# microphone.net
KiCad netlist of a schematic drawn in Altium Designer
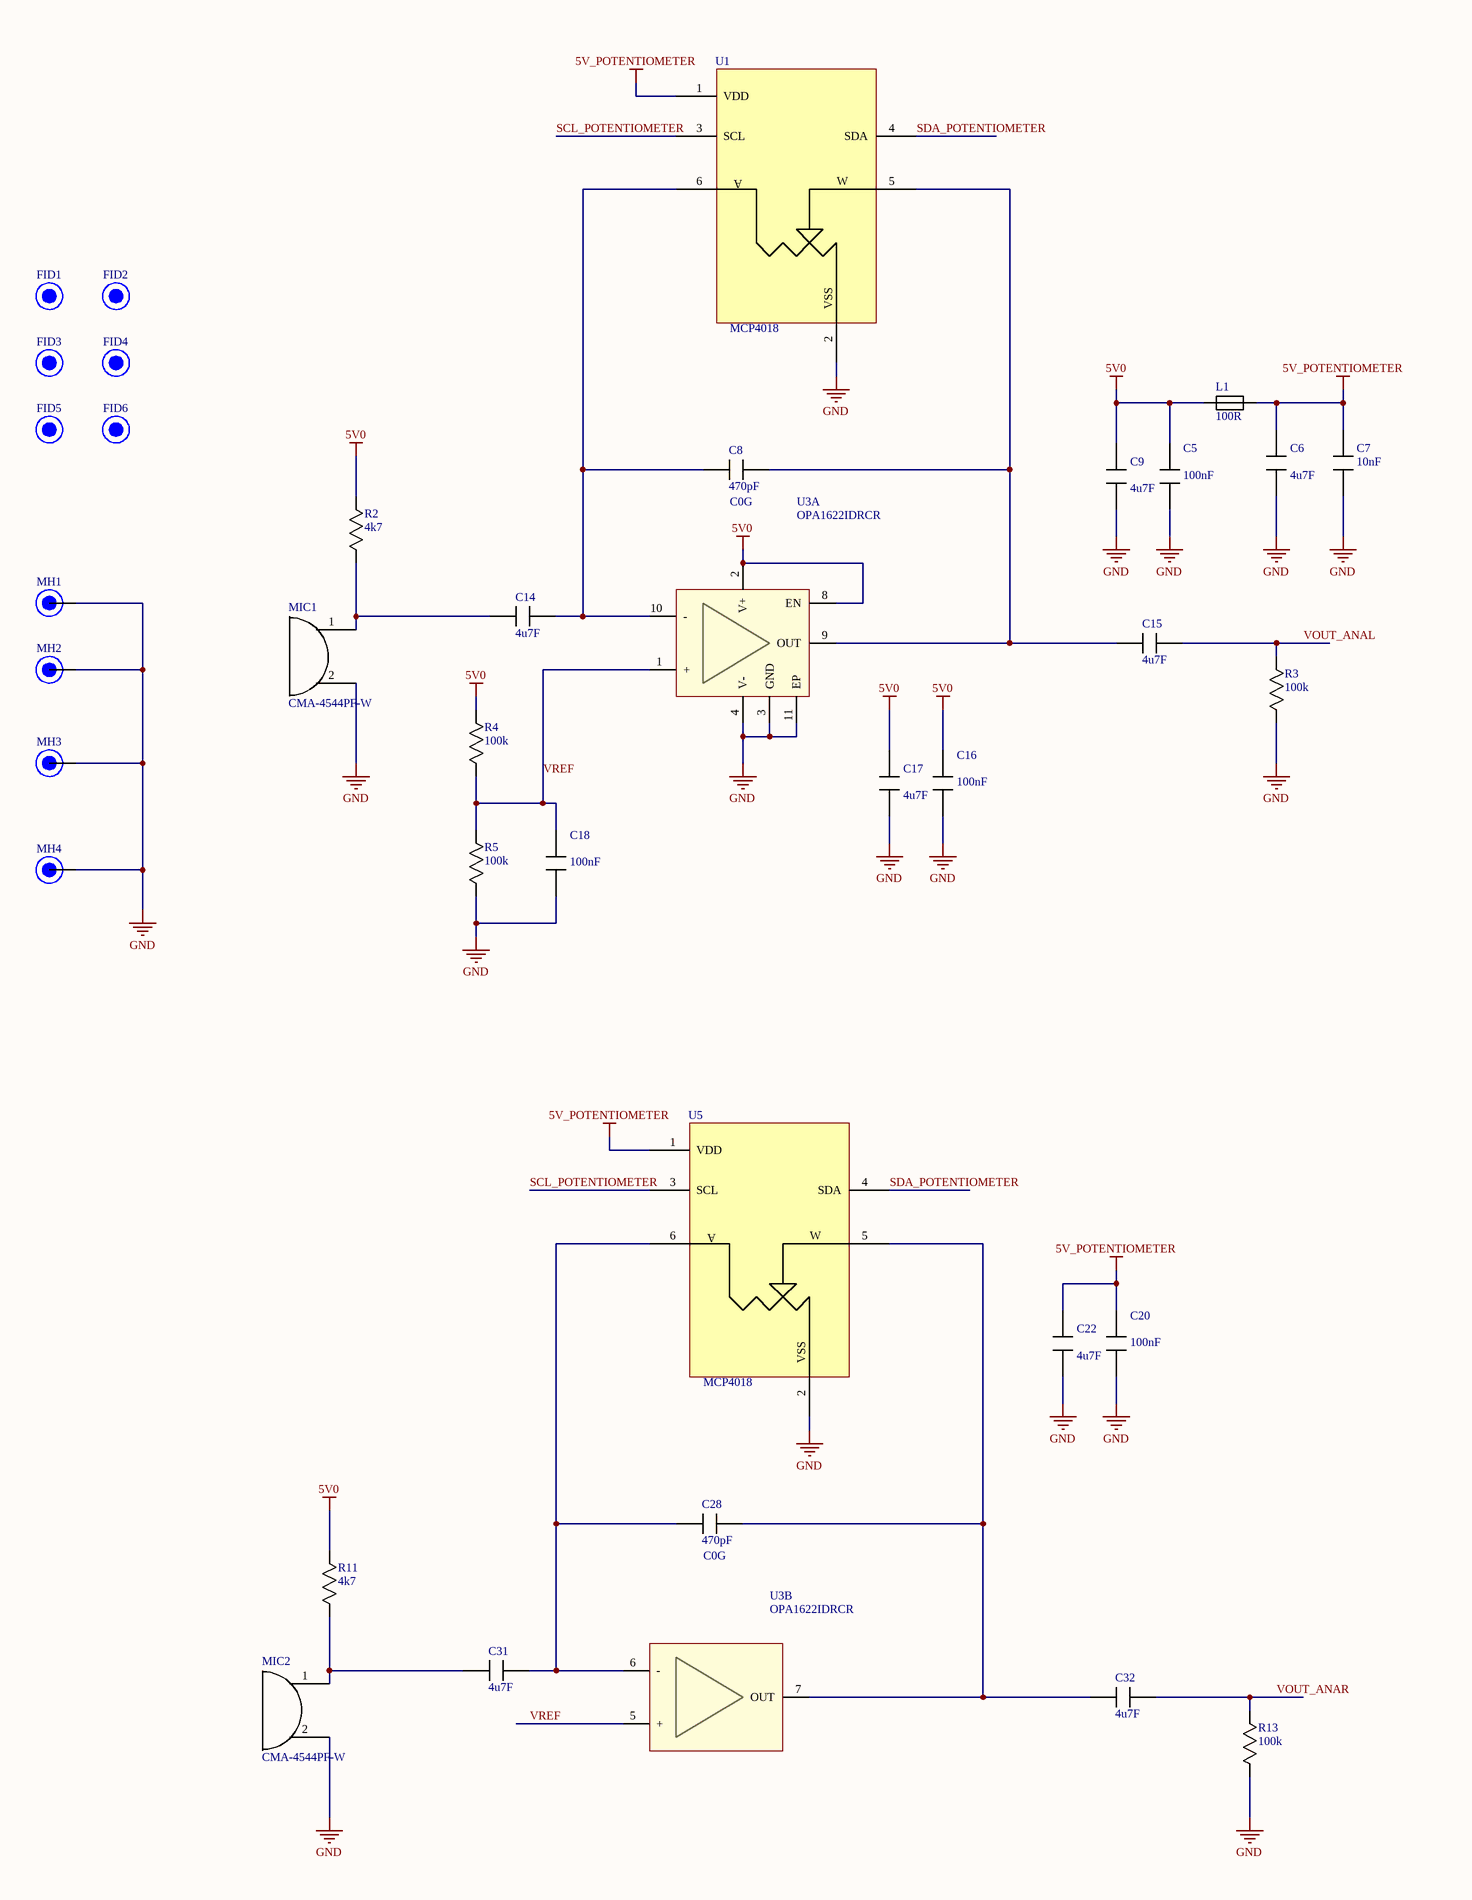
[diagram p0: microphone.SchDoc, left]
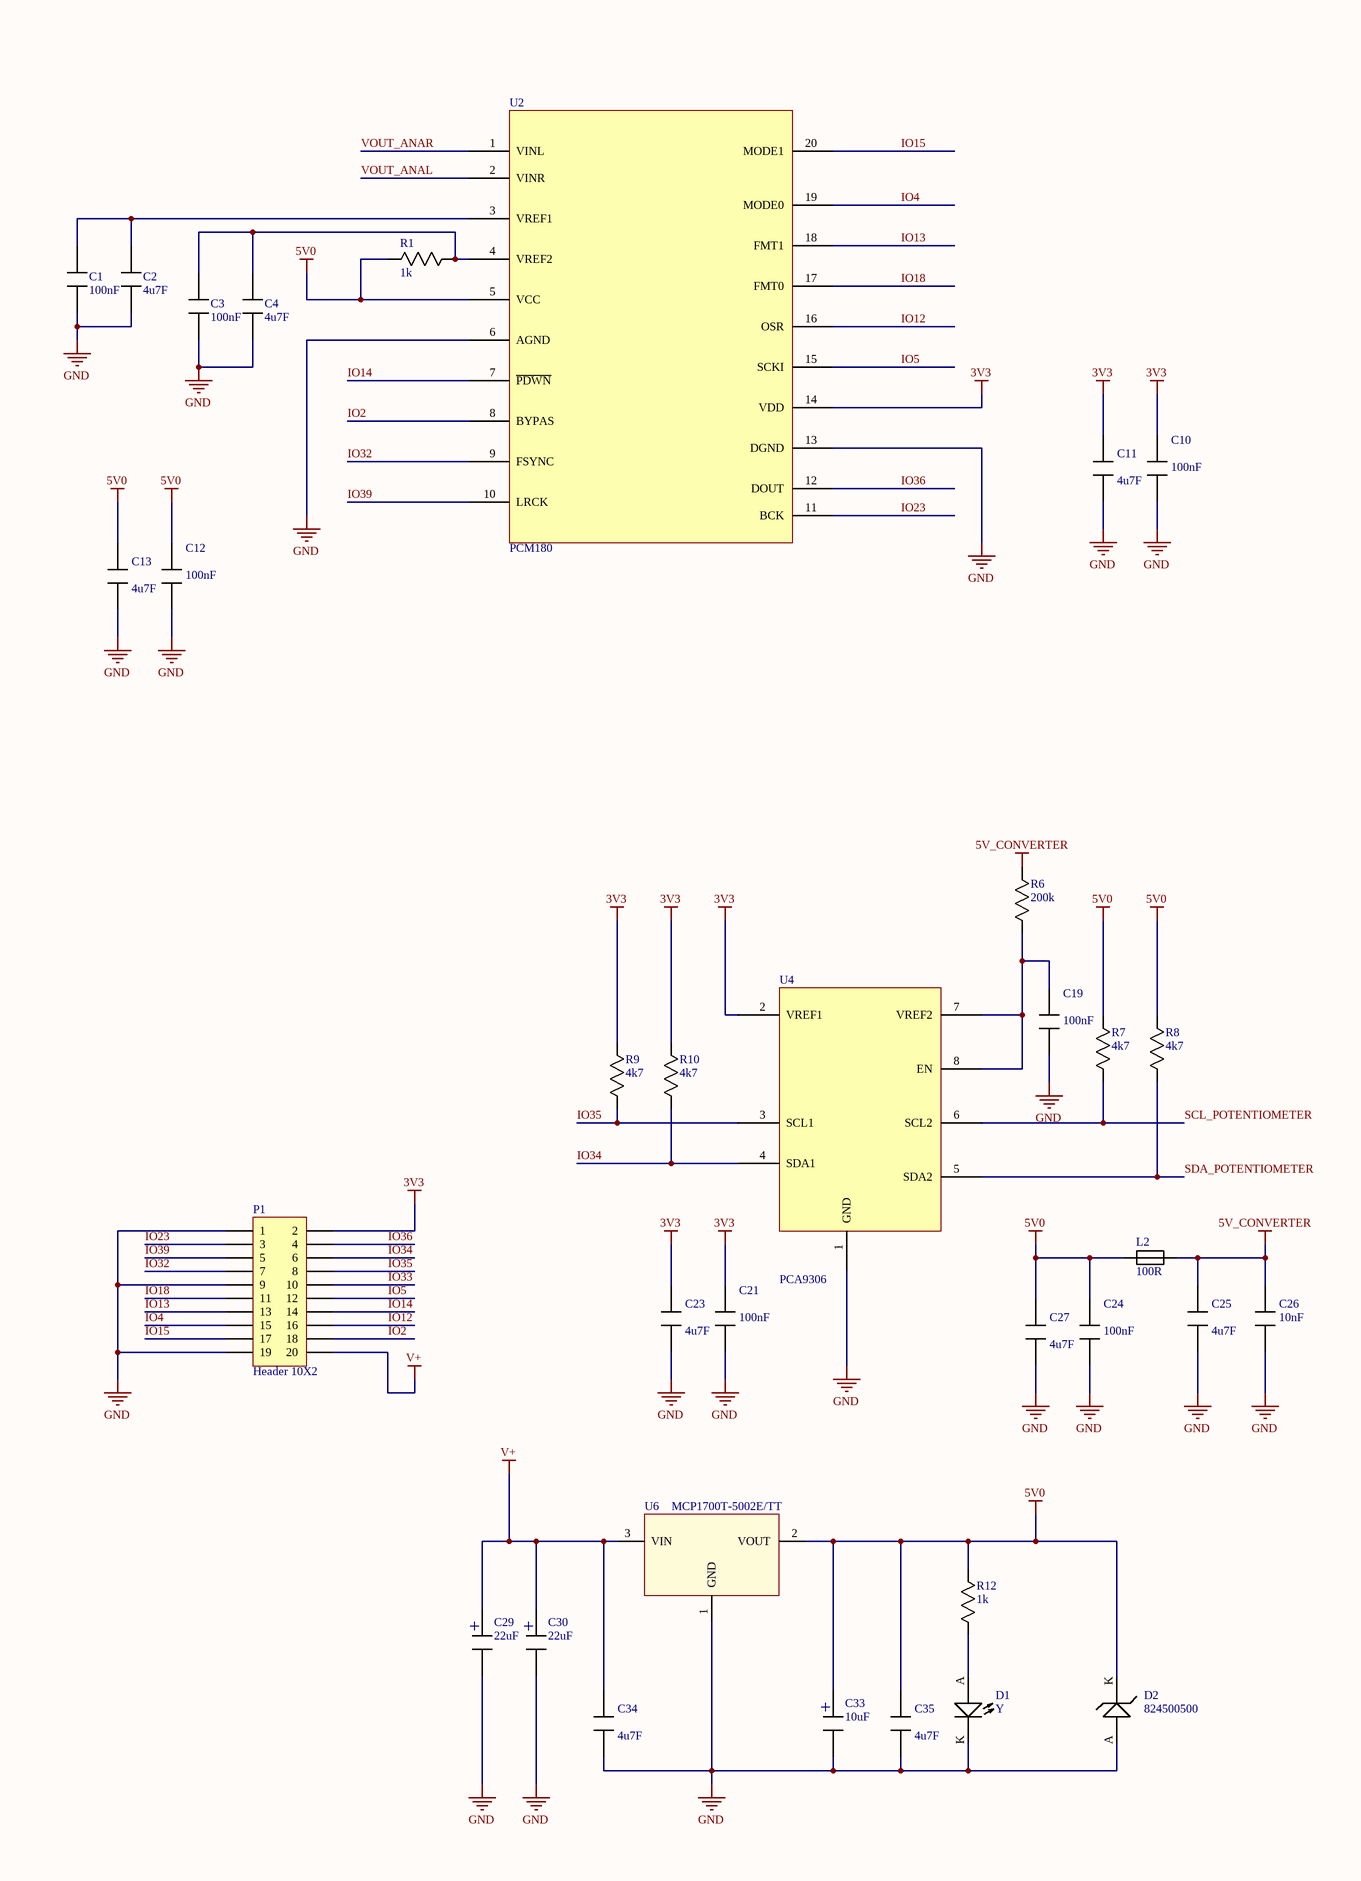
[diagram p1: microphone.SchDoc, right]

(export (version "E")
  (design (tool "Eeschema 10.0.6"))
  (components
    (comp (ref "C1")
      (value "100nF")
      (footprint "0603")
      (description "Capacitor")
      (fields (field (name "MFG") "Samsung"))
      (libsource (lib "INTER_2014") (part "Capacitor"))
    )
    (comp (ref "C2")
      (value "4u7F")
      (footprint "0805")
      (description "Capacitor")
      (fields (field (name "MFG") "Samsung"))
      (libsource (lib "ADAPTONE_CARTE_DE_SON") (part "Capacitor"))
    )
    (comp (ref "C3")
      (value "100nF")
      (footprint "0603")
      (description "Capacitor")
      (fields (field (name "MFG") "Samsung"))
      (libsource (lib "INTER_2014") (part "Capacitor"))
    )
    (comp (ref "C4")
      (value "4u7F")
      (footprint "0805")
      (description "Capacitor")
      (fields (field (name "MFG") "Samsung"))
      (libsource (lib "ADAPTONE_CARTE_DE_SON") (part "Capacitor"))
    )
    (comp (ref "C5")
      (value "100nF")
      (footprint "0603")
      (description "Capacitor")
      (fields (field (name "MFG") "Samsung"))
      (libsource (lib "INTER_2014") (part "Capacitor"))
    )
    (comp (ref "C6")
      (value "4u7F")
      (footprint "0805")
      (description "Capacitor")
      (fields (field (name "MFG") "Samsung"))
      (libsource (lib "ADAPTONE_CARTE_DE_SON") (part "Capacitor"))
    )
    (comp (ref "C7")
      (value "10nF")
      (footprint "0603")
      (description "Capacitor")
      (fields (field (name "MFG") "Murata"))
      (libsource (lib "ADAPTONE_CARTE_DE_SON") (part "Capacitor"))
    )
    (comp (ref "C8")
      (value "470pF")
      (footprint "0603")
      (description "Capacitor")
      (fields (field (name "MFG") "Samsung") (field (name "TYPE") "C0G"))
      (libsource (lib "INTER_2014") (part "Capacitor"))
    )
    (comp (ref "C9")
      (value "4u7F")
      (footprint "0805")
      (description "Capacitor")
      (fields (field (name "MFG") "Samsung"))
      (libsource (lib "ADAPTONE_CARTE_DE_SON") (part "Capacitor"))
    )
    (comp (ref "C10")
      (value "100nF")
      (footprint "0603")
      (description "Capacitor")
      (fields (field (name "MFG") "Samsung"))
      (libsource (lib "INTER_2014") (part "Capacitor"))
    )
    (comp (ref "C11")
      (value "4u7F")
      (footprint "0805")
      (description "Capacitor")
      (fields (field (name "MFG") "Samsung"))
      (libsource (lib "ADAPTONE_CARTE_DE_SON") (part "Capacitor"))
    )
    (comp (ref "C12")
      (value "100nF")
      (footprint "0603")
      (description "Capacitor")
      (fields (field (name "MFG") "Samsung"))
      (libsource (lib "INTER_2014") (part "Capacitor"))
    )
    (comp (ref "C13")
      (value "4u7F")
      (footprint "0805")
      (description "Capacitor")
      (fields (field (name "MFG") "Samsung"))
      (libsource (lib "ADAPTONE_CARTE_DE_SON") (part "Capacitor"))
    )
    (comp (ref "C14")
      (value "4u7F")
      (footprint "0805")
      (description "Capacitor")
      (fields (field (name "MFG") "Samsung"))
      (libsource (lib "INTER_2014") (part "Capacitor"))
    )
    (comp (ref "C15")
      (value "4u7F")
      (footprint "0805")
      (description "Capacitor")
      (fields (field (name "MFG") "Samsung"))
      (libsource (lib "INTER_2014") (part "Capacitor"))
    )
    (comp (ref "C16")
      (value "100nF")
      (footprint "0603")
      (description "Capacitor")
      (fields (field (name "MFG") "Samsung"))
      (libsource (lib "INTER_2014") (part "Capacitor"))
    )
    (comp (ref "C17")
      (value "4u7F")
      (footprint "0805")
      (description "Capacitor")
      (fields (field (name "MFG") "Samsung"))
      (libsource (lib "ADAPTONE_CARTE_DE_SON") (part "Capacitor"))
    )
    (comp (ref "C18")
      (value "100nF")
      (footprint "0603")
      (description "Capacitor")
      (fields (field (name "MFG") "Samsung"))
      (libsource (lib "INTER_2014") (part "Capacitor"))
    )
    (comp (ref "C19")
      (value "100nF")
      (footprint "0603")
      (description "Capacitor")
      (fields (field (name "MFG") "Samsung"))
      (libsource (lib "INTER_2014") (part "Capacitor"))
    )
    (comp (ref "C20")
      (value "100nF")
      (footprint "0603")
      (description "Capacitor")
      (fields (field (name "MFG") "Samsung"))
      (libsource (lib "INTER_2014") (part "Capacitor"))
    )
    (comp (ref "C21")
      (value "100nF")
      (footprint "0603")
      (description "Capacitor")
      (fields (field (name "MFG") "Samsung"))
      (libsource (lib "INTER_2014") (part "Capacitor"))
    )
    (comp (ref "C22")
      (value "4u7F")
      (footprint "0805")
      (description "Capacitor")
      (fields (field (name "MFG") "Samsung"))
      (libsource (lib "ADAPTONE_CARTE_DE_SON") (part "Capacitor"))
    )
    (comp (ref "C23")
      (value "4u7F")
      (footprint "0805")
      (description "Capacitor")
      (fields (field (name "MFG") "Samsung"))
      (libsource (lib "ADAPTONE_CARTE_DE_SON") (part "Capacitor"))
    )
    (comp (ref "C24")
      (value "100nF")
      (footprint "0603")
      (description "Capacitor")
      (fields (field (name "MFG") "Samsung"))
      (libsource (lib "INTER_2014") (part "Capacitor"))
    )
    (comp (ref "C25")
      (value "4u7F")
      (footprint "0805")
      (description "Capacitor")
      (fields (field (name "MFG") "Samsung"))
      (libsource (lib "ADAPTONE_CARTE_DE_SON") (part "Capacitor"))
    )
    (comp (ref "C26")
      (value "10nF")
      (footprint "0603")
      (description "Capacitor")
      (fields (field (name "MFG") "Murata"))
      (libsource (lib "ADAPTONE_CARTE_DE_SON") (part "Capacitor"))
    )
    (comp (ref "C27")
      (value "4u7F")
      (footprint "0805")
      (description "Capacitor")
      (fields (field (name "MFG") "Samsung"))
      (libsource (lib "ADAPTONE_CARTE_DE_SON") (part "Capacitor"))
    )
    (comp (ref "C28")
      (value "470pF")
      (footprint "0603")
      (description "Capacitor")
      (fields (field (name "MFG") "Samsung") (field (name "TYPE") "C0G"))
      (libsource (lib "INTER_2014") (part "Capacitor"))
    )
    (comp (ref "C29")
      (value "22uF")
      (footprint "CAP_RAD_SMD_DIA157")
      (description "Capacitor")
      (fields (field (name "MFG") "Panasonic") (field (name "Comment") "Capacitor_Polarized"))
      (libsource (lib "ADAPTONE_CARTE_DE_SON") (part "Capacitor_Polarized"))
    )
    (comp (ref "C30")
      (value "22uF")
      (footprint "CAP_RAD_SMD_DIA157")
      (description "Capacitor")
      (fields (field (name "MFG") "Panasonic") (field (name "Comment") "Capacitor_Polarized"))
      (libsource (lib "ADAPTONE_CARTE_DE_SON") (part "Capacitor_Polarized"))
    )
    (comp (ref "C31")
      (value "4u7F")
      (footprint "0805")
      (description "Capacitor")
      (fields (field (name "MFG") "Samsung"))
      (libsource (lib "INTER_2014") (part "Capacitor"))
    )
    (comp (ref "C32")
      (value "4u7F")
      (footprint "0805")
      (description "Capacitor")
      (fields (field (name "MFG") "Samsung"))
      (libsource (lib "INTER_2014") (part "Capacitor"))
    )
    (comp (ref "C33")
      (value "10uF")
      (footprint "CAP_RAD_SMD_DIA157")
      (description "Capacitor")
      (fields (field (name "MFG") "Nichicon") (field (name "Comment") "Capacitor_Polarized"))
      (libsource (lib "ADAPTONE_CARTE_DE_SON") (part "Capacitor_Polarized"))
    )
    (comp (ref "C34")
      (value "4u7F")
      (footprint "0805")
      (description "Capacitor")
      (fields (field (name "MFG") "Samsung"))
      (libsource (lib "ADAPTONE_CARTE_DE_SON") (part "Capacitor"))
    )
    (comp (ref "C35")
      (value "4u7F")
      (footprint "0805")
      (description "Capacitor")
      (fields (field (name "MFG") "Samsung"))
      (libsource (lib "ADAPTONE_CARTE_DE_SON") (part "Capacitor"))
    )
    (comp (ref "D1")
      (value "Diode_LED")
      (footprint "0805_LED")
      (description "LED")
      (fields (field (name "MFG") "Osram") (field (name "TYPE") "Y"))
      (libsource (lib "ADAPTONE_CARTE_DE_SON") (part "Diode_LED"))
    )
    (comp (ref "D2")
      (value "Diode_zener")
      (footprint "DIODE_DO-214AC/SMA")
      (description "Diode")
      (fields (field (name "MFG") "Wurth") (field (name "MFG_PN") "824500500"))
      (libsource (lib "ADAPTONE_CARTE_DE_SON") (part "Diode_zener"))
    )
    (comp (ref "FID1")
      (value "Fiducial 1mm")
      (footprint "FID_1MM")
      (description "FID - 1MM")
      (fields (field (name "CREATEDBY") "Jonathan Bouchard") (field (name "VERIFIEDBY") "Alexandre Imbeault"))
      (libsource (lib "S7CAS_Lib2019_REV1_00") (part "FID_1MM"))
    )
    (comp (ref "FID2")
      (value "Fiducial 1mm")
      (footprint "FID_1MM")
      (description "FID - 1MM")
      (fields (field (name "CREATEDBY") "Jonathan Bouchard") (field (name "VERIFIEDBY") "Alexandre Imbeault"))
      (libsource (lib "S7CAS_Lib2019_REV1_00") (part "FID_1MM"))
    )
    (comp (ref "FID3")
      (value "Fiducial 1mm")
      (footprint "FID_1MM")
      (description "FID - 1MM")
      (fields (field (name "CREATEDBY") "Jonathan Bouchard") (field (name "VERIFIEDBY") "Alexandre Imbeault"))
      (libsource (lib "S7CAS_Lib2019_REV1_00") (part "FID_1MM"))
    )
    (comp (ref "FID4")
      (value "Fiducial 1mm")
      (footprint "FID_1MM")
      (description "FID - 1MM")
      (fields (field (name "CREATEDBY") "Jonathan Bouchard") (field (name "VERIFIEDBY") "Alexandre Imbeault"))
      (libsource (lib "S7CAS_Lib2019_REV1_00") (part "FID_1MM"))
    )
    (comp (ref "FID5")
      (value "Fiducial 1mm")
      (footprint "FID_1MM")
      (description "FID - 1MM")
      (fields (field (name "CREATEDBY") "Jonathan Bouchard") (field (name "VERIFIEDBY") "Alexandre Imbeault"))
      (libsource (lib "S7CAS_Lib2019_REV1_00") (part "FID_1MM"))
    )
    (comp (ref "FID6")
      (value "Fiducial 1mm")
      (footprint "FID_1MM")
      (description "FID - 1MM")
      (fields (field (name "CREATEDBY") "Jonathan Bouchard") (field (name "VERIFIEDBY") "Alexandre Imbeault"))
      (libsource (lib "S7CAS_Lib2019_REV1_00") (part "FID_1MM"))
    )
    (comp (ref "L1")
      (value "100R")
      (footprint "0603")
      (description "Ferrite")
      (fields (field (name "MFG") "Bourns"))
      (libsource (lib "ADAPTONE_CARTE_DE_SON") (part "Ferrite"))
    )
    (comp (ref "L2")
      (value "100R")
      (footprint "0603")
      (description "Ferrite")
      (fields (field (name "MFG") "Bourns"))
      (libsource (lib "ADAPTONE_CARTE_DE_SON") (part "Ferrite"))
    )
    (comp (ref "MH1")
      (value "Mounting Hole 6-32")
      (footprint "MH_ENG_6-32")
      (description "MH - Mounting Hole 6-32")
      (fields (field (name "CREATEDBY") "Jonathan Bouchard") (field (name "VERIFIEDBY") "Alexandre Imbeault"))
      (libsource (lib "S7CAS_Lib2019_REV1_00") (part "MH_6-32"))
    )
    (comp (ref "MH2")
      (value "Mounting Hole 6-32")
      (footprint "MH_ENG_6-32")
      (description "MH - Mounting Hole 6-32")
      (fields (field (name "CREATEDBY") "Jonathan Bouchard") (field (name "VERIFIEDBY") "Alexandre Imbeault"))
      (libsource (lib "S7CAS_Lib2019_REV1_00") (part "MH_6-32"))
    )
    (comp (ref "MH3")
      (value "Mounting Hole 6-32")
      (footprint "MH_ENG_6-32")
      (description "MH - Mounting Hole 6-32")
      (fields (field (name "CREATEDBY") "Jonathan Bouchard") (field (name "VERIFIEDBY") "Alexandre Imbeault"))
      (libsource (lib "S7CAS_Lib2019_REV1_00") (part "MH_6-32"))
    )
    (comp (ref "MH4")
      (value "Mounting Hole 6-32")
      (footprint "MH_ENG_6-32")
      (description "MH - Mounting Hole 6-32")
      (fields (field (name "CREATEDBY") "Jonathan Bouchard") (field (name "VERIFIEDBY") "Alexandre Imbeault"))
      (libsource (lib "S7CAS_Lib2019_REV1_00") (part "MH_6-32"))
    )
    (comp (ref "MIC1")
      (value "CMA-4544PF-W")
      (footprint "MIC")
      (fields
        (field (name "MFG") "CUI Inc.")
        (field (name "CREATEDBY") "Emile Laplante")
        (field (name "VERIFIEDBY") "*")
      )
      (libsource (lib "LIB_ADAPTONE_EMILE_LAPLANTE") (part "CMA-4544PF-W"))
    )
    (comp (ref "MIC2")
      (value "CMA-4544PF-W")
      (footprint "MIC")
      (fields
        (field (name "MFG") "CUI Inc.")
        (field (name "CREATEDBY") "Emile Laplante")
        (field (name "VERIFIEDBY") "*")
      )
      (libsource (lib "LIB_ADAPTONE_EMILE_LAPLANTE") (part "CMA-4544PF-W"))
    )
    (comp (ref "P1")
      (value "Header 10X2")
      (footprint "HDR2X10")
      (description "Header, 10-Pin, Dual row")
      (fields (field (name "PUBLISHER") "Altium Limited"))
      (libsource (lib "Miscellaneous Connectors") (part "Header 10X2"))
    )
    (comp (ref "R1")
      (value "1k")
      (footprint "0603")
      (description "Resistor")
      (fields (field (name "MFG") "Yageo"))
      (libsource (lib "INTER_2014") (part "Resistor"))
    )
    (comp (ref "R2")
      (value "4k7")
      (footprint "0603")
      (description "Resistor")
      (fields (field (name "MFG") "Yageo"))
      (libsource (lib "INTER_2014") (part "Resistor"))
    )
    (comp (ref "R3")
      (value "100k")
      (footprint "0603")
      (description "Resistor")
      (fields (field (name "MFG") "Yageo"))
      (libsource (lib "INTER_2014") (part "Resistor"))
    )
    (comp (ref "R4")
      (value "100k")
      (footprint "0603")
      (description "Resistor")
      (fields (field (name "MFG") "Yageo"))
      (libsource (lib "INTER_2014") (part "Resistor"))
    )
    (comp (ref "R5")
      (value "100k")
      (footprint "0603")
      (description "Resistor")
      (fields (field (name "MFG") "Yageo"))
      (libsource (lib "INTER_2014") (part "Resistor"))
    )
    (comp (ref "R6")
      (value "200k")
      (footprint "0603")
      (description "Resistor")
      (fields (field (name "MFG") "Panasonic Electronic Components"))
      (libsource (lib "INTER_2014") (part "Resistor"))
    )
    (comp (ref "R7")
      (value "4k7")
      (footprint "0603")
      (description "Resistor")
      (fields (field (name "MFG") "Yageo"))
      (libsource (lib "INTER_2014") (part "Resistor"))
    )
    (comp (ref "R8")
      (value "4k7")
      (footprint "0603")
      (description "Resistor")
      (fields (field (name "MFG") "Yageo"))
      (libsource (lib "INTER_2014") (part "Resistor"))
    )
    (comp (ref "R9")
      (value "4k7")
      (footprint "0603")
      (description "Resistor")
      (fields (field (name "MFG") "Yageo"))
      (libsource (lib "INTER_2014") (part "Resistor"))
    )
    (comp (ref "R10")
      (value "4k7")
      (footprint "0603")
      (description "Resistor")
      (fields (field (name "MFG") "Yageo"))
      (libsource (lib "INTER_2014") (part "Resistor"))
    )
    (comp (ref "R11")
      (value "4k7")
      (footprint "0603")
      (description "Resistor")
      (fields (field (name "MFG") "Yageo"))
      (libsource (lib "INTER_2014") (part "Resistor"))
    )
    (comp (ref "R12")
      (value "1k")
      (footprint "0603")
      (description "Resistor")
      (fields (field (name "MFG") "Yageo"))
      (libsource (lib "ADAPTONE_CARTE_DE_SON") (part "Resistor"))
    )
    (comp (ref "R13")
      (value "100k")
      (footprint "0603")
      (description "Resistor")
      (fields (field (name "MFG") "Yageo"))
      (libsource (lib "INTER_2014") (part "Resistor"))
    )
    (comp (ref "U1")
      (value "MCP4018")
      (footprint "6-TSSOP")
      (fields
        (field (name "MFG") "Microchip Technology")
        (field (name "MFG PART NUMBER") "MCP4018T-503E/LT")
        (field (name "CREATEDBY") "Emile Laplante")
        (field (name "VERIFIEDBY") "*")
      )
      (libsource (lib "LIB_ADAPTONE_EMILE_LAPLANTE") (part "MCP4018"))
    )
    (comp (ref "U2")
      (value "PCM180")
      (footprint "20-SSOP")
      (fields
        (field (name "MFG") "Texas Instruments")
        (field (name "MFG PART NUMBER") "PCM1802DBR")
        (field (name "CREATEDBY") "Emile Laplante")
        (field (name "VERIFIEDBY") "*")
      )
      (libsource (lib "LIB_ADAPTONE_EMILE_LAPLANTE") (part "PCM180"))
    )
    (comp (ref "U3")
      (value "OPA1622")
      (footprint "10-VFDFN")
      (description "Dual amplifier (headphone driver)")
      (fields (field (name "MFG") "Texas Instruments") (field (name "MFG_PN") "OPA1622IDRCR"))
      (libsource (lib "LIB_ADAPTONE_PASCAL_LEMIEUX") (part "OPA1622"))
    )
    (comp (ref "U4")
      (value "PCA9306")
      (footprint "8-XFDFN")
      (fields
        (field (name "MFG") "Txas Instruments")
        (field (name "MFG PART NUMBER") "PCA9306DQER")
        (field (name "CREATEDBY") "Emile Laplante")
        (field (name "VERIFIEDBY") "*")
      )
      (libsource (lib "LIB_ADAPTONE_EMILE_LAPLANTE") (part "PCA9306"))
    )
    (comp (ref "U5")
      (value "MCP4018")
      (footprint "6-TSSOP")
      (fields
        (field (name "MFG") "Microchip Technology")
        (field (name "MFG PART NUMBER") "MCP4018T-503E/LT")
        (field (name "CREATEDBY") "Emile Laplante")
        (field (name "VERIFIEDBY") "*")
      )
      (libsource (lib "LIB_ADAPTONE_EMILE_LAPLANTE") (part "MCP4018"))
    )
    (comp (ref "U6")
      (value "MCP1700")
      (footprint "SOT23_132")
      (description "Linear voltage regulator")
      (fields (field (name "MFG") "Microchip") (field (name "MFG_PN") "MCP1700T-5002E/TT"))
      (libsource (lib "ADAPTONE_CARTE_DE_SON") (part "MCP1700"))
    )
  )
  (nets
    (net (code "1") (name "/IO2") (class "Default")
      (node (ref "P1") (pin "18") (pinfunction "18_18") (pintype "passive"))
      (node (ref "U2") (pin "8") (pinfunction "BYPAS_8") (pintype "passive"))
    )
    (net (code "2") (name "/IO4") (class "Default")
      (node (ref "P1") (pin "15") (pinfunction "15_15") (pintype "passive"))
      (node (ref "U2") (pin "19") (pinfunction "MODE0_19") (pintype "passive"))
    )
    (net (code "3") (name "/IO5") (class "Default")
      (node (ref "P1") (pin "12") (pinfunction "12_12") (pintype "passive"))
      (node (ref "U2") (pin "15") (pinfunction "SCKI_15") (pintype "passive"))
    )
    (net (code "4") (name "/IO12") (class "Default")
      (node (ref "P1") (pin "16") (pinfunction "16_16") (pintype "passive"))
      (node (ref "U2") (pin "16") (pinfunction "OSR_16") (pintype "passive"))
    )
    (net (code "5") (name "/IO13") (class "Default")
      (node (ref "P1") (pin "13") (pinfunction "13_13") (pintype "passive"))
      (node (ref "U2") (pin "18") (pinfunction "FMT1_18") (pintype "passive"))
    )
    (net (code "6") (name "/IO14") (class "Default")
      (node (ref "P1") (pin "14") (pinfunction "14_14") (pintype "passive"))
      (node (ref "U2") (pin "7") (pinfunction "~{PDWN}_7") (pintype "passive"))
    )
    (net (code "7") (name "/IO15") (class "Default")
      (node (ref "P1") (pin "17") (pinfunction "17_17") (pintype "passive"))
      (node (ref "U2") (pin "20") (pinfunction "MODE1_20") (pintype "passive"))
    )
    (net (code "8") (name "/IO18") (class "Default")
      (node (ref "P1") (pin "11") (pinfunction "11_11") (pintype "passive"))
      (node (ref "U2") (pin "17") (pinfunction "FMT0_17") (pintype "passive"))
    )
    (net (code "9") (name "/IO23") (class "Default")
      (node (ref "P1") (pin "3") (pinfunction "3_3") (pintype "passive"))
      (node (ref "U2") (pin "11") (pinfunction "BCK_11") (pintype "passive"))
    )
    (net (code "10") (name "/IO32") (class "Default")
      (node (ref "P1") (pin "7") (pinfunction "7_7") (pintype "passive"))
      (node (ref "U2") (pin "9") (pinfunction "FSYNC_9") (pintype "passive"))
    )
    (net (code "11") (name "/IO33") (class "Default")
      (node (ref "P1") (pin "10") (pinfunction "10_10") (pintype "passive"))
    )
    (net (code "12") (name "/IO34") (class "Default")
      (node (ref "P1") (pin "6") (pinfunction "6_6") (pintype "passive"))
      (node (ref "R10") (pin "2") (pintype "passive"))
      (node (ref "U4") (pin "4") (pinfunction "SDA1_4") (pintype "passive"))
    )
    (net (code "13") (name "/IO35") (class "Default")
      (node (ref "P1") (pin "8") (pinfunction "8_8") (pintype "passive"))
      (node (ref "R9") (pin "2") (pintype "passive"))
      (node (ref "U4") (pin "3") (pinfunction "SCL1_3") (pintype "passive"))
    )
    (net (code "14") (name "/IO36") (class "Default")
      (node (ref "P1") (pin "4") (pinfunction "4_4") (pintype "passive"))
      (node (ref "U2") (pin "12") (pinfunction "DOUT_12") (pintype "passive"))
    )
    (net (code "15") (name "/IO39") (class "Default")
      (node (ref "P1") (pin "5") (pinfunction "5_5") (pintype "passive"))
      (node (ref "U2") (pin "10") (pinfunction "LRCK_10") (pintype "passive"))
    )
    (net (code "16") (name "/SCL_POTENTIOMETER") (class "Default")
      (node (ref "R7") (pin "2") (pintype "passive"))
      (node (ref "U1") (pin "3") (pinfunction "SCL_3") (pintype "passive"))
      (node (ref "U4") (pin "6") (pinfunction "SCL2_6") (pintype "passive"))
      (node (ref "U5") (pin "3") (pinfunction "SCL_3") (pintype "passive"))
    )
    (net (code "17") (name "/SDA_POTENTIOMETER") (class "Default")
      (node (ref "R8") (pin "2") (pintype "passive"))
      (node (ref "U1") (pin "4") (pinfunction "SDA_4") (pintype "passive"))
      (node (ref "U4") (pin "5") (pinfunction "SDA2_5") (pintype "passive"))
      (node (ref "U5") (pin "4") (pinfunction "SDA_4") (pintype "passive"))
    )
    (net (code "18") (name "/VOUT_ANAL") (class "Default")
      (node (ref "C15") (pin "2") (pintype "passive"))
      (node (ref "R3") (pin "2") (pintype "passive"))
      (node (ref "U2") (pin "2") (pinfunction "VINR_2") (pintype "passive"))
    )
    (net (code "19") (name "/VOUT_ANAR") (class "Default")
      (node (ref "C32") (pin "2") (pintype "passive"))
      (node (ref "R13") (pin "2") (pintype "passive"))
      (node (ref "U2") (pin "1") (pinfunction "VINL_1") (pintype "passive"))
    )
    (net (code "20") (name "/VREF") (class "Default")
      (node (ref "C18") (pin "1") (pintype "passive"))
      (node (ref "R4") (pin "1") (pintype "passive"))
      (node (ref "R5") (pin "2") (pintype "passive"))
      (node (ref "U3") (pin "1") (pinfunction "+_1") (pintype "passive"))
      (node (ref "U3") (pin "5") (pinfunction "+_5") (pintype "passive"))
    )
    (net (code "21") (name "3V3") (class "Default")
      (node (ref "C10") (pin "1") (pintype "passive"))
      (node (ref "C11") (pin "1") (pintype "passive"))
      (node (ref "C21") (pin "1") (pintype "passive"))
      (node (ref "C23") (pin "1") (pintype "passive"))
      (node (ref "P1") (pin "2") (pinfunction "2_2") (pintype "passive"))
      (node (ref "R10") (pin "1") (pintype "passive"))
      (node (ref "R9") (pin "1") (pintype "passive"))
      (node (ref "U2") (pin "14") (pinfunction "VDD_14") (pintype "passive"))
      (node (ref "U4") (pin "2") (pinfunction "VREF1_2") (pintype "passive"))
    )
    (net (code "22") (name "5V0") (class "Default")
      (node (ref "C12") (pin "1") (pintype "passive"))
      (node (ref "C13") (pin "1") (pintype "passive"))
      (node (ref "C16") (pin "1") (pintype "passive"))
      (node (ref "C17") (pin "1") (pintype "passive"))
      (node (ref "C24") (pin "1") (pintype "passive"))
      (node (ref "C27") (pin "1") (pintype "passive"))
      (node (ref "C33") (pin "+") (pintype "passive"))
      (node (ref "C35") (pin "1") (pintype "passive"))
      (node (ref "C5") (pin "1") (pintype "passive"))
      (node (ref "C9") (pin "1") (pintype "passive"))
      (node (ref "D2") (pin "K") (pintype "passive"))
      (node (ref "L1") (pin "1") (pintype "passive"))
      (node (ref "L2") (pin "1") (pintype "passive"))
      (node (ref "R1") (pin "2") (pintype "passive"))
      (node (ref "R11") (pin "1") (pintype "passive"))
      (node (ref "R12") (pin "2") (pintype "passive"))
      (node (ref "R2") (pin "1") (pintype "passive"))
      (node (ref "R4") (pin "2") (pintype "passive"))
      (node (ref "R7") (pin "1") (pintype "passive"))
      (node (ref "R8") (pin "1") (pintype "passive"))
      (node (ref "U2") (pin "5") (pinfunction "VCC_5") (pintype "passive"))
      (node (ref "U3") (pin "2") (pinfunction "V+_2") (pintype "passive"))
      (node (ref "U3") (pin "8") (pinfunction "EN_8") (pintype "passive"))
      (node (ref "U6") (pin "2") (pinfunction "VOUT_2") (pintype "passive"))
    )
    (net (code "23") (name "5V_CONVERTER") (class "Default")
      (node (ref "C25") (pin "1") (pintype "passive"))
      (node (ref "C26") (pin "1") (pintype "passive"))
      (node (ref "L2") (pin "2") (pintype "passive"))
      (node (ref "R6") (pin "1") (pintype "passive"))
    )
    (net (code "24") (name "5V_POTENTIOMETER") (class "Default")
      (node (ref "C20") (pin "1") (pintype "passive"))
      (node (ref "C22") (pin "1") (pintype "passive"))
      (node (ref "C6") (pin "1") (pintype "passive"))
      (node (ref "C7") (pin "1") (pintype "passive"))
      (node (ref "L1") (pin "2") (pintype "passive"))
      (node (ref "U1") (pin "1") (pinfunction "VDD_1") (pintype "passive"))
      (node (ref "U5") (pin "1") (pinfunction "VDD_1") (pintype "passive"))
    )
    (net (code "25") (name "GND") (class "Default")
      (node (ref "C1") (pin "1") (pintype "passive"))
      (node (ref "C10") (pin "2") (pintype "passive"))
      (node (ref "C11") (pin "2") (pintype "passive"))
      (node (ref "C12") (pin "2") (pintype "passive"))
      (node (ref "C13") (pin "2") (pintype "passive"))
      (node (ref "C16") (pin "2") (pintype "passive"))
      (node (ref "C17") (pin "2") (pintype "passive"))
      (node (ref "C18") (pin "2") (pintype "passive"))
      (node (ref "C19") (pin "2") (pintype "passive"))
      (node (ref "C2") (pin "1") (pintype "passive"))
      (node (ref "C20") (pin "2") (pintype "passive"))
      (node (ref "C21") (pin "2") (pintype "passive"))
      (node (ref "C22") (pin "2") (pintype "passive"))
      (node (ref "C23") (pin "2") (pintype "passive"))
      (node (ref "C24") (pin "2") (pintype "passive"))
      (node (ref "C25") (pin "2") (pintype "passive"))
      (node (ref "C26") (pin "2") (pintype "passive"))
      (node (ref "C27") (pin "2") (pintype "passive"))
      (node (ref "C29") (pin "-") (pintype "passive"))
      (node (ref "C3") (pin "1") (pintype "passive"))
      (node (ref "C30") (pin "-") (pintype "passive"))
      (node (ref "C33") (pin "-") (pintype "passive"))
      (node (ref "C34") (pin "2") (pintype "passive"))
      (node (ref "C35") (pin "2") (pintype "passive"))
      (node (ref "C4") (pin "1") (pintype "passive"))
      (node (ref "C5") (pin "2") (pintype "passive"))
      (node (ref "C6") (pin "2") (pintype "passive"))
      (node (ref "C7") (pin "2") (pintype "passive"))
      (node (ref "C9") (pin "2") (pintype "passive"))
      (node (ref "D1") (pin "K") (pintype "passive"))
      (node (ref "D2") (pin "A") (pintype "passive"))
      (node (ref "MH1") (pin "1") (pinfunction "1_1") (pintype "passive"))
      (node (ref "MH2") (pin "1") (pinfunction "1_1") (pintype "passive"))
      (node (ref "MH3") (pin "1") (pinfunction "1_1") (pintype "passive"))
      (node (ref "MH4") (pin "1") (pinfunction "1_1") (pintype "passive"))
      (node (ref "MIC1") (pin "2") (pintype "passive"))
      (node (ref "MIC2") (pin "2") (pintype "passive"))
      (node (ref "P1") (pin "1") (pinfunction "1_1") (pintype "passive"))
      (node (ref "P1") (pin "19") (pinfunction "19_19") (pintype "passive"))
      (node (ref "P1") (pin "9") (pinfunction "9_9") (pintype "passive"))
      (node (ref "R13") (pin "1") (pintype "passive"))
      (node (ref "R3") (pin "1") (pintype "passive"))
      (node (ref "R5") (pin "1") (pintype "passive"))
      (node (ref "U1") (pin "2") (pinfunction "VSS_2") (pintype "passive"))
      (node (ref "U2") (pin "13") (pinfunction "DGND_13") (pintype "passive"))
      (node (ref "U2") (pin "6") (pinfunction "AGND_6") (pintype "passive"))
      (node (ref "U3") (pin "11") (pinfunction "EP_11") (pintype "passive"))
      (node (ref "U3") (pin "3") (pinfunction "GND_3") (pintype "passive"))
      (node (ref "U3") (pin "4") (pinfunction "V-_4") (pintype "passive"))
      (node (ref "U4") (pin "1") (pinfunction "GND_1") (pintype "passive"))
      (node (ref "U5") (pin "2") (pinfunction "VSS_2") (pintype "passive"))
      (node (ref "U6") (pin "1") (pinfunction "GND_1") (pintype "passive"))
    )
    (net (code "26") (name "Net-(C14-Pad1)") (class "Default")
      (node (ref "C14") (pin "1") (pintype "passive"))
      (node (ref "MIC1") (pin "1") (pintype "passive"))
      (node (ref "R2") (pin "2") (pintype "passive"))
    )
    (net (code "27") (name "Net-(C31-Pad1)") (class "Default")
      (node (ref "C31") (pin "1") (pintype "passive"))
      (node (ref "MIC2") (pin "1") (pintype "passive"))
      (node (ref "R11") (pin "2") (pintype "passive"))
    )
    (net (code "28") (name "Net-(D1-PadA)") (class "Default")
      (node (ref "D1") (pin "A") (pintype "passive"))
      (node (ref "R12") (pin "1") (pintype "passive"))
    )
    (net (code "29") (name "Net-(U1-A)") (class "Default")
      (node (ref "C14") (pin "2") (pintype "passive"))
      (node (ref "C8") (pin "1") (pintype "passive"))
      (node (ref "U1") (pin "6") (pinfunction "A_6") (pintype "passive"))
      (node (ref "U3") (pin "10") (pinfunction "-_10") (pintype "passive"))
    )
    (net (code "30") (name "Net-(U1-W)") (class "Default")
      (node (ref "C15") (pin "1") (pintype "passive"))
      (node (ref "C8") (pin "2") (pintype "passive"))
      (node (ref "U1") (pin "5") (pinfunction "W_5") (pintype "passive"))
      (node (ref "U3") (pin "9") (pinfunction "OUT_9") (pintype "passive"))
    )
    (net (code "31") (name "Net-(U2-VREF1)") (class "Default")
      (node (ref "C1") (pin "2") (pintype "passive"))
      (node (ref "C2") (pin "2") (pintype "passive"))
      (node (ref "U2") (pin "3") (pinfunction "VREF1_3") (pintype "passive"))
    )
    (net (code "32") (name "Net-(U2-VREF2)") (class "Default")
      (node (ref "C3") (pin "2") (pintype "passive"))
      (node (ref "C4") (pin "2") (pintype "passive"))
      (node (ref "R1") (pin "1") (pintype "passive"))
      (node (ref "U2") (pin "4") (pinfunction "VREF2_4") (pintype "passive"))
    )
    (net (code "33") (name "Net-(U3B--)") (class "Default")
      (node (ref "C28") (pin "1") (pintype "passive"))
      (node (ref "C31") (pin "2") (pintype "passive"))
      (node (ref "U3") (pin "6") (pinfunction "-_6") (pintype "passive"))
      (node (ref "U5") (pin "6") (pinfunction "A_6") (pintype "passive"))
    )
    (net (code "34") (name "Net-(U3B-OUT)") (class "Default")
      (node (ref "C28") (pin "2") (pintype "passive"))
      (node (ref "C32") (pin "1") (pintype "passive"))
      (node (ref "U3") (pin "7") (pinfunction "OUT_7") (pintype "passive"))
      (node (ref "U5") (pin "5") (pinfunction "W_5") (pintype "passive"))
    )
    (net (code "35") (name "Net-(U4-EN)") (class "Default")
      (node (ref "C19") (pin "1") (pintype "passive"))
      (node (ref "R6") (pin "2") (pintype "passive"))
      (node (ref "U4") (pin "7") (pinfunction "VREF2_7") (pintype "passive"))
      (node (ref "U4") (pin "8") (pinfunction "EN_8") (pintype "passive"))
    )
    (net (code "36") (name "V+") (class "Default")
      (node (ref "C29") (pin "+") (pintype "passive"))
      (node (ref "C30") (pin "+") (pintype "passive"))
      (node (ref "C34") (pin "1") (pintype "passive"))
      (node (ref "P1") (pin "20") (pinfunction "20_20") (pintype "passive"))
      (node (ref "U6") (pin "3") (pinfunction "VIN_3") (pintype "passive"))
    )
  )
)
